# HEBoard_schematic_Ver2.net
KiCad netlist of a schematic drawn in Altium Designer
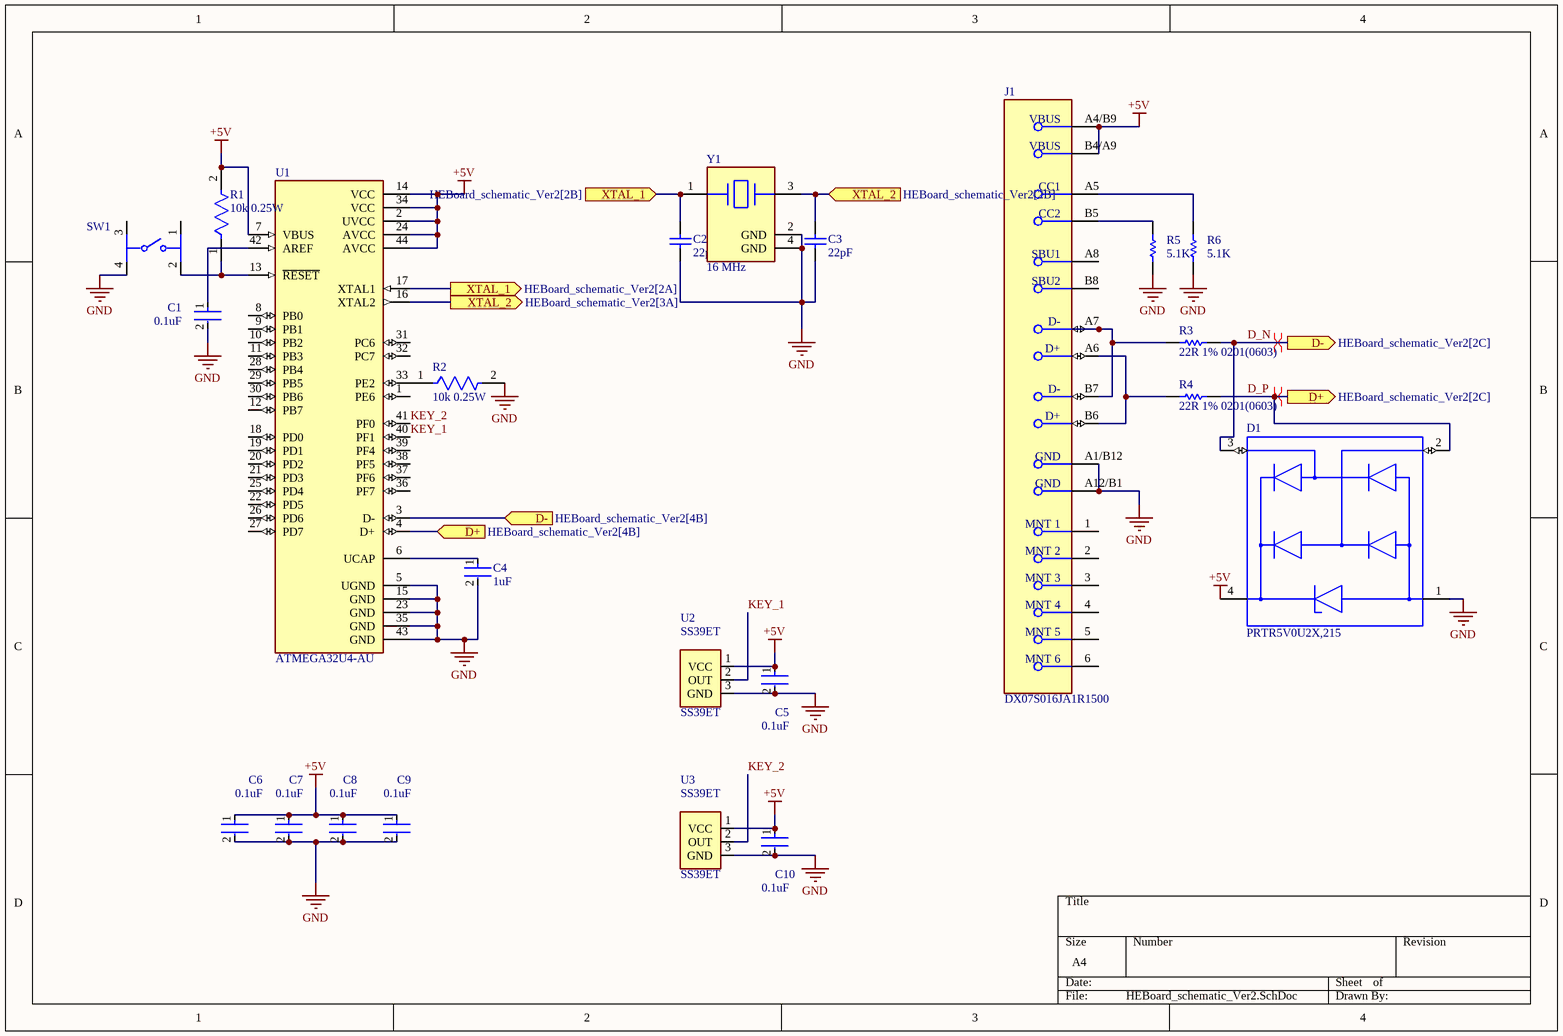
[diagram p0: HEBoard_schematic_Ver2.SchDoc]

(export (version "E")
  (design (tool "Eeschema 10.0.6"))
  (components
    (comp (ref "C1")
      (value "0.1uF")
      (footprint "FP-GRM033-0_03-IPC_C")
      (description "Chip Multilayer Ceramic Capacitors for General Purpose, 0201, 0.10uF, X5R, 15%, 10%, 10V")
      (fields (field (name "TOLERANCE") "10%") (field (name "VOLTAGE") "10V"))
      (libsource (lib "Altium Content Vault") (part "b4654b650e69147ec39a6b967a45e02"))
    )
    (comp (ref "C2")
      (value "22pF")
      (footprint "CAPC1006X50X20ML10T10")
      (fields
        (field (name "PART NUMBER") "0402ZK220GBSTR..")
        (field (name "MANUFACTURER") "AVX Interconnect / Elco")
      )
      (libsource (lib "Altium Content Vault") (part "CAP"))
    )
    (comp (ref "C3")
      (value "22pF")
      (footprint "CAPC1006X50X20ML10T10")
      (fields
        (field (name "PART NUMBER") "0402ZK220GBSTR..")
        (field (name "MANUFACTURER") "AVX Interconnect / Elco")
      )
      (libsource (lib "Altium Content Vault") (part "CAP"))
    )
    (comp (ref "C4")
      (value "1uF")
      (footprint "FP-GRM15-0_1-MFG")
      (description "CAP CER 1UF 10V X5R 0402")
      (fields
        (field (name "OCTOPART") "https://octopart.com/grm155r61a105ke15d-murata-197442")
        (field (name "MANUFACTURER PART NUMBER") "GRM155R61A105KE15D")
      )
      (libsource (lib "Altium Content Vault") (part "02cd4be3c70576c341d710602a673aa"))
    )
    (comp (ref "C5")
      (value "0.1uF")
      (footprint "FP-GRM033-0_03-IPC_C")
      (description "Chip Multilayer Ceramic Capacitors for General Purpose, 0201, 0.10uF, X5R, 15%, 10%, 10V")
      (fields (field (name "TOLERANCE") "10%") (field (name "VOLTAGE") "10V"))
      (libsource (lib "Altium Content Vault") (part "b4654b650e69147ec39a6b967a45e02"))
    )
    (comp (ref "C6")
      (value "0.1uF")
      (footprint "FP-GRM033-0_03-IPC_C")
      (description "Chip Multilayer Ceramic Capacitors for General Purpose, 0201, 0.10uF, X5R, 15%, 10%, 10V")
      (fields (field (name "TOLERANCE") "10%") (field (name "VOLTAGE") "10V"))
      (libsource (lib "Altium Content Vault") (part "b4654b650e69147ec39a6b967a45e02"))
    )
    (comp (ref "C7")
      (value "0.1uF")
      (footprint "FP-GRM033-0_03-IPC_C")
      (description "Chip Multilayer Ceramic Capacitors for General Purpose, 0201, 0.10uF, X5R, 15%, 10%, 10V")
      (fields (field (name "TOLERANCE") "10%") (field (name "VOLTAGE") "10V"))
      (libsource (lib "Altium Content Vault") (part "b4654b650e69147ec39a6b967a45e02"))
    )
    (comp (ref "C8")
      (value "0.1uF")
      (footprint "FP-GRM033-0_03-IPC_C")
      (description "Chip Multilayer Ceramic Capacitors for General Purpose, 0201, 0.10uF, X5R, 15%, 10%, 10V")
      (fields (field (name "TOLERANCE") "10%") (field (name "VOLTAGE") "10V"))
      (libsource (lib "Altium Content Vault") (part "b4654b650e69147ec39a6b967a45e02"))
    )
    (comp (ref "C9")
      (value "0.1uF")
      (footprint "FP-GRM033-0_03-IPC_C")
      (description "Chip Multilayer Ceramic Capacitors for General Purpose, 0201, 0.10uF, X5R, 15%, 10%, 10V")
      (fields (field (name "TOLERANCE") "10%") (field (name "VOLTAGE") "10V"))
      (libsource (lib "Altium Content Vault") (part "b4654b650e69147ec39a6b967a45e02"))
    )
    (comp (ref "C10")
      (value "0.1uF")
      (footprint "FP-GRM033-0_03-IPC_C")
      (description "Chip Multilayer Ceramic Capacitors for General Purpose, 0201, 0.10uF, X5R, 15%, 10%, 10V")
      (fields (field (name "TOLERANCE") "10%") (field (name "VOLTAGE") "10V"))
      (libsource (lib "Altium Content Vault") (part "b4654b650e69147ec39a6b967a45e02"))
    )
    (comp (ref "D1")
      (value "PRTR5V0U2X,215")
      (footprint "FP-SOT143B-MFG")
      (description "TVS DIODE 5.5V SOT143B")
      (libsource (lib "Altium Content Vault") (part "31e4fa1655694efd507c8a671e666ef"))
    )
    (comp (ref "J1")
      (value "DX07S016JA1R1500")
      (footprint "FP-DX07S016JA1R1500-MFG")
      (description "CONN RCP USB2.0 TYP C 24P SMD RA")
      (libsource (lib "Altium Content Vault") (part "7f3e9989102a0f22bff9cb010881d34"))
    )
    (comp (ref "R1")
      (value "10k 0.25W")
      (footprint "FP-RNCP0805-IPC_C")
      (description "10kΩ ±1% 0.25W 0805 High Power Anti-Sulfur Thin Film Chip Resistor")
      (fields (field (name "TOLERANCE") "1%"))
      (libsource (lib "Altium Content Vault") (part "1029c3af85768c4190bb7ad29bc67b5"))
    )
    (comp (ref "R2")
      (value "10k 0.25W")
      (footprint "FP-RNCP0805-IPC_C")
      (description "10kΩ ±1% 0.25W 0805 High Power Anti-Sulfur Thin Film Chip Resistor")
      (fields (field (name "TOLERANCE") "1%"))
      (libsource (lib "Altium Content Vault") (part "1029c3af85768c4190bb7ad29bc67b5"))
    )
    (comp (ref "R3")
      (value "22R 1% 0201(0603)")
      (footprint "RESC0201(0603)_M")
      (description "22R 0.05W 1% 0201 (0603 Metric)  SMD")
      (fields (field (name "POWER") "0.05 W") (field (name "TOLERANCE") "1 %"))
      (libsource (lib "Altium Content Vault") (part "RES"))
    )
    (comp (ref "R4")
      (value "22R 1% 0201(0603)")
      (footprint "RESC0201(0603)_M")
      (description "22R 0.05W 1% 0201 (0603 Metric)  SMD")
      (fields (field (name "POWER") "0.05 W") (field (name "TOLERANCE") "1 %"))
      (libsource (lib "Altium Content Vault") (part "RES"))
    )
    (comp (ref "R5")
      (value "5.1K")
      (footprint "RESC2013X60X30NL20T20")
      (fields (field (name "MANUFACTURER") "KOA Speer") (field (name "PART NUMBER") "RK73H2ATTD5101F"))
      (libsource (lib "Altium Content Vault") (part "RES"))
    )
    (comp (ref "R6")
      (value "5.1K")
      (footprint "RESC2013X60X30NL20T20")
      (fields (field (name "MANUFACTURER") "KOA Speer") (field (name "PART NUMBER") "RK73H2ATTD5101F"))
      (libsource (lib "Altium Content Vault") (part "RES"))
    )
    (comp (ref "SW1")
      (value "~")
      (footprint "FP-PTS645SM43SMTR92LFS-MFG")
      (description "SWITCH TACTILE SPST-NO 0.05A 12V")
      (libsource (lib "Altium Content Vault") (part "1adf0dd01260c80cf25a44bfd6b99ba"))
    )
    (comp (ref "U1")
      (value "ATMEGA32U4-AU")
      (footprint "QFP80P1200X1200X120-44N")
      (description "AVR AVRÂ® ATmega Microcontroller IC 8-Bit 16MHz 32KB (16K x 16) FLASH 44-TQFP (10x10)")
      (fields (field (name "MF") "Microchip Technology"))
      (libsource (lib "Schlib1") (part "ATMEGA32U4-AU"))
    )
    (comp (ref "U2")
      (value "SS39ET")
      (footprint "CHRY-MX1A-11NW_V")
      (description "analog Hall Effect Sensor 1.5 mA 2.7 - 6.5 V dc ¦ Honeywell SS39ET")
      (fields (field (name "MF") "Honeywell Sensing and Productivity Solutions"))
      (libsource (lib "Schlib1") (part "SS39ET"))
    )
    (comp (ref "U3")
      (value "SS39ET")
      (footprint "CHRY-MX1A-11NW_V")
      (description "analog Hall Effect Sensor 1.5 mA 2.7 - 6.5 V dc ¦ Honeywell SS39ET")
      (fields (field (name "MF") "Honeywell Sensing and Productivity Solutions"))
      (libsource (lib "Schlib1") (part "SS39ET"))
    )
    (comp (ref "Y1")
      (value "16 MHz")
      (footprint "FP-ABM8G-MFG")
      (description "Crystal 16MHz ±30ppm (Tol) ±30ppm (Stability) 10pF FUND 80Ω 4-Pin SMD T/R")
      (libsource (lib "Altium Content Vault") (part "48e526d86b7f2615d98721063c72f49"))
    )
  )
  (nets
    (net (code "1") (name "+5V") (class "Default")
      (node (ref "C10") (pin "1") (pinfunction "1_1") (pintype "passive"))
      (node (ref "C5") (pin "1") (pinfunction "1_1") (pintype "passive"))
      (node (ref "C6") (pin "1") (pinfunction "1_1") (pintype "passive"))
      (node (ref "C7") (pin "1") (pinfunction "1_1") (pintype "passive"))
      (node (ref "C8") (pin "1") (pinfunction "1_1") (pintype "passive"))
      (node (ref "C9") (pin "1") (pinfunction "1_1") (pintype "passive"))
      (node (ref "D1") (pin "4") (pinfunction "VCC_4") (pintype "power_in"))
      (node (ref "J1") (pin "A4/B9") (pinfunction "VBUS_A4/B9") (pintype "power_in"))
      (node (ref "J1") (pin "B4/A9") (pinfunction "VBUS_B4/A9") (pintype "power_in"))
      (node (ref "R1") (pin "2") (pinfunction "2_2") (pintype "passive"))
      (node (ref "U1") (pin "14") (pinfunction "VCC_14") (pintype "power_in"))
      (node (ref "U1") (pin "2") (pinfunction "UVCC_2") (pintype "power_in"))
      (node (ref "U1") (pin "24") (pinfunction "AVCC_24") (pintype "power_in"))
      (node (ref "U1") (pin "34") (pinfunction "VCC_34") (pintype "power_in"))
      (node (ref "U1") (pin "44") (pinfunction "AVCC_44") (pintype "power_in"))
      (node (ref "U1") (pin "7") (pinfunction "VBUS_7") (pintype "input"))
      (node (ref "U2") (pin "1") (pinfunction "VCC_1") (pintype "passive"))
      (node (ref "U3") (pin "1") (pinfunction "VCC_1") (pintype "passive"))
    )
    (net (code "2") (name "/D_N") (class "Default")
      (node (ref "D1") (pin "3") (pinfunction "I/O_2_3") (pintype "bidirectional"))
      (node (ref "R3") (pin "2") (pinfunction "2_2") (pintype "passive"))
      (node (ref "U1") (pin "3") (pinfunction "D-_3") (pintype "bidirectional"))
    )
    (net (code "3") (name "/D_P") (class "Default")
      (node (ref "D1") (pin "2") (pinfunction "I/O_1_2") (pintype "bidirectional"))
      (node (ref "R4") (pin "2") (pinfunction "2_2") (pintype "passive"))
      (node (ref "U1") (pin "4") (pinfunction "D+_4") (pintype "bidirectional"))
    )
    (net (code "4") (name "/KEY_1") (class "Default")
      (node (ref "U1") (pin "40") (pinfunction "PF1_40") (pintype "bidirectional"))
      (node (ref "U2") (pin "2") (pinfunction "OUT_2") (pintype "passive"))
    )
    (net (code "5") (name "/KEY_2") (class "Default")
      (node (ref "U1") (pin "41") (pinfunction "PF0_41") (pintype "bidirectional"))
      (node (ref "U3") (pin "2") (pinfunction "OUT_2") (pintype "passive"))
    )
    (net (code "6") (name "/XTAL_1") (class "Default")
      (node (ref "C2") (pin "2") (pinfunction "2_2") (pintype "passive"))
      (node (ref "U1") (pin "17") (pinfunction "XTAL1_17") (pintype "input"))
      (node (ref "Y1") (pin "1") (pinfunction "1_1") (pintype "passive"))
    )
    (net (code "7") (name "/XTAL_2") (class "Default")
      (node (ref "C3") (pin "2") (pinfunction "2_2") (pintype "passive"))
      (node (ref "U1") (pin "16") (pinfunction "XTAL2_16") (pintype "output"))
      (node (ref "Y1") (pin "3") (pinfunction "3_3") (pintype "passive"))
    )
    (net (code "8") (name "GND") (class "Default")
      (node (ref "C1") (pin "2") (pinfunction "2_2") (pintype "passive"))
      (node (ref "C10") (pin "2") (pinfunction "2_2") (pintype "passive"))
      (node (ref "C2") (pin "1") (pinfunction "1_1") (pintype "passive"))
      (node (ref "C3") (pin "1") (pinfunction "1_1") (pintype "passive"))
      (node (ref "C4") (pin "2") (pinfunction "2_2") (pintype "passive"))
      (node (ref "C5") (pin "2") (pinfunction "2_2") (pintype "passive"))
      (node (ref "C6") (pin "2") (pinfunction "2_2") (pintype "passive"))
      (node (ref "C7") (pin "2") (pinfunction "2_2") (pintype "passive"))
      (node (ref "C8") (pin "2") (pinfunction "2_2") (pintype "passive"))
      (node (ref "C9") (pin "2") (pinfunction "2_2") (pintype "passive"))
      (node (ref "D1") (pin "1") (pinfunction "GND_1") (pintype "power_in"))
      (node (ref "J1") (pin "A1/B12") (pinfunction "GND_A1/B12") (pintype "power_in"))
      (node (ref "J1") (pin "A12/B1") (pinfunction "GND_A12/B1") (pintype "power_in"))
      (node (ref "R2") (pin "2") (pinfunction "2_2") (pintype "passive"))
      (node (ref "R5") (pin "1") (pinfunction "1_1") (pintype "passive"))
      (node (ref "R6") (pin "1") (pinfunction "1_1") (pintype "passive"))
      (node (ref "SW1") (pin "4") (pinfunction "4_4") (pintype "passive"))
      (node (ref "U1") (pin "15") (pinfunction "GND_15") (pintype "power_in"))
      (node (ref "U1") (pin "23") (pinfunction "GND_23") (pintype "power_in"))
      (node (ref "U1") (pin "35") (pinfunction "GND_35") (pintype "power_in"))
      (node (ref "U1") (pin "43") (pinfunction "GND_43") (pintype "power_in"))
      (node (ref "U1") (pin "5") (pinfunction "UGND_5") (pintype "power_in"))
      (node (ref "U2") (pin "3") (pinfunction "GND_3") (pintype "passive"))
      (node (ref "U3") (pin "3") (pinfunction "GND_3") (pintype "passive"))
      (node (ref "Y1") (pin "2") (pinfunction "GND_2") (pintype "power_in"))
      (node (ref "Y1") (pin "4") (pinfunction "GND_4") (pintype "power_in"))
    )
    (net (code "9") (name "Net-(J1-CC1)") (class "Default")
      (node (ref "J1") (pin "A5") (pinfunction "CC1_A5") (pintype "passive"))
      (node (ref "R6") (pin "2") (pinfunction "2_2") (pintype "passive"))
    )
    (net (code "10") (name "Net-(J1-CC2)") (class "Default")
      (node (ref "J1") (pin "B5") (pinfunction "CC2_B5") (pintype "passive"))
      (node (ref "R5") (pin "2") (pinfunction "2_2") (pintype "passive"))
    )
    (net (code "11") (name "Net-(J1-D+-PadA6)") (class "Default")
      (node (ref "J1") (pin "A6") (pinfunction "D+_A6") (pintype "bidirectional"))
      (node (ref "J1") (pin "B6") (pinfunction "D+_B6") (pintype "bidirectional"))
      (node (ref "R4") (pin "1") (pinfunction "1_1") (pintype "passive"))
    )
    (net (code "12") (name "Net-(J1-D--PadA7)") (class "Default")
      (node (ref "J1") (pin "A7") (pinfunction "D-_A7") (pintype "bidirectional"))
      (node (ref "J1") (pin "B7") (pinfunction "D-_B7") (pintype "bidirectional"))
      (node (ref "R3") (pin "1") (pinfunction "1_1") (pintype "passive"))
    )
    (net (code "13") (name "Net-(U1-AREF)") (class "Default")
      (node (ref "C1") (pin "1") (pinfunction "1_1") (pintype "passive"))
      (node (ref "U1") (pin "42") (pinfunction "AREF_42") (pintype "input"))
    )
    (net (code "14") (name "Net-(U1-PE2)") (class "Default")
      (node (ref "R2") (pin "1") (pinfunction "1_1") (pintype "passive"))
      (node (ref "U1") (pin "33") (pinfunction "PE2_33") (pintype "bidirectional"))
    )
    (net (code "15") (name "Net-(U1-UCAP)") (class "Default")
      (node (ref "C4") (pin "1") (pinfunction "1_1") (pintype "passive"))
      (node (ref "U1") (pin "6") (pinfunction "UCAP_6") (pintype "passive"))
    )
    (net (code "16") (name "Net-(U1-~{RESET})") (class "Default")
      (node (ref "R1") (pin "1") (pinfunction "1_1") (pintype "passive"))
      (node (ref "SW1") (pin "2") (pinfunction "2_2") (pintype "passive"))
      (node (ref "U1") (pin "13") (pinfunction "~{RESET}_13") (pintype "input"))
    )
    (net (code "17") (name "unconnected-(J1-MNT_1-Pad1)") (class "Default")
      (node (ref "J1") (pin "1") (pinfunction "MNT_1_1") (pintype "passive"))
    )
    (net (code "18") (name "unconnected-(J1-MNT_2-Pad2)") (class "Default")
      (node (ref "J1") (pin "2") (pinfunction "MNT_2_2") (pintype "passive"))
    )
    (net (code "19") (name "unconnected-(J1-MNT_3-Pad3)") (class "Default")
      (node (ref "J1") (pin "3") (pinfunction "MNT_3_3") (pintype "passive"))
    )
    (net (code "20") (name "unconnected-(J1-MNT_4-Pad4)") (class "Default")
      (node (ref "J1") (pin "4") (pinfunction "MNT_4_4") (pintype "passive"))
    )
    (net (code "21") (name "unconnected-(J1-MNT_5-Pad5)") (class "Default")
      (node (ref "J1") (pin "5") (pinfunction "MNT_5_5") (pintype "passive"))
    )
    (net (code "22") (name "unconnected-(J1-MNT_6-Pad6)") (class "Default")
      (node (ref "J1") (pin "6") (pinfunction "MNT_6_6") (pintype "passive"))
    )
    (net (code "23") (name "unconnected-(J1-SBU1-PadA8)") (class "Default")
      (node (ref "J1") (pin "A8") (pinfunction "SBU1_A8") (pintype "passive"))
    )
    (net (code "24") (name "unconnected-(J1-SBU2-PadB8)") (class "Default")
      (node (ref "J1") (pin "B8") (pinfunction "SBU2_B8") (pintype "passive"))
    )
    (net (code "25") (name "unconnected-(SW1-Pad1)") (class "Default")
      (node (ref "SW1") (pin "1") (pinfunction "1_1") (pintype "passive"))
    )
    (net (code "26") (name "unconnected-(SW1-Pad3)") (class "Default")
      (node (ref "SW1") (pin "3") (pinfunction "3_3") (pintype "passive"))
    )
    (net (code "27") (name "unconnected-(U1-PB0-Pad8)") (class "Default")
      (node (ref "U1") (pin "8") (pinfunction "PB0_8") (pintype "bidirectional"))
    )
    (net (code "28") (name "unconnected-(U1-PB1-Pad9)") (class "Default")
      (node (ref "U1") (pin "9") (pinfunction "PB1_9") (pintype "bidirectional"))
    )
    (net (code "29") (name "unconnected-(U1-PB2-Pad10)") (class "Default")
      (node (ref "U1") (pin "10") (pinfunction "PB2_10") (pintype "bidirectional"))
    )
    (net (code "30") (name "unconnected-(U1-PB3-Pad11)") (class "Default")
      (node (ref "U1") (pin "11") (pinfunction "PB3_11") (pintype "bidirectional"))
    )
    (net (code "31") (name "unconnected-(U1-PB4-Pad28)") (class "Default")
      (node (ref "U1") (pin "28") (pinfunction "PB4_28") (pintype "bidirectional"))
    )
    (net (code "32") (name "unconnected-(U1-PB5-Pad29)") (class "Default")
      (node (ref "U1") (pin "29") (pinfunction "PB5_29") (pintype "bidirectional"))
    )
    (net (code "33") (name "unconnected-(U1-PB6-Pad30)") (class "Default")
      (node (ref "U1") (pin "30") (pinfunction "PB6_30") (pintype "bidirectional"))
    )
    (net (code "34") (name "unconnected-(U1-PB7-Pad12)") (class "Default")
      (node (ref "U1") (pin "12") (pinfunction "PB7_12") (pintype "bidirectional"))
    )
    (net (code "35") (name "unconnected-(U1-PC6-Pad31)") (class "Default")
      (node (ref "U1") (pin "31") (pinfunction "PC6_31") (pintype "bidirectional"))
    )
    (net (code "36") (name "unconnected-(U1-PC7-Pad32)") (class "Default")
      (node (ref "U1") (pin "32") (pinfunction "PC7_32") (pintype "bidirectional"))
    )
    (net (code "37") (name "unconnected-(U1-PD0-Pad18)") (class "Default")
      (node (ref "U1") (pin "18") (pinfunction "PD0_18") (pintype "bidirectional"))
    )
    (net (code "38") (name "unconnected-(U1-PD1-Pad19)") (class "Default")
      (node (ref "U1") (pin "19") (pinfunction "PD1_19") (pintype "bidirectional"))
    )
    (net (code "39") (name "unconnected-(U1-PD2-Pad20)") (class "Default")
      (node (ref "U1") (pin "20") (pinfunction "PD2_20") (pintype "bidirectional"))
    )
    (net (code "40") (name "unconnected-(U1-PD3-Pad21)") (class "Default")
      (node (ref "U1") (pin "21") (pinfunction "PD3_21") (pintype "bidirectional"))
    )
    (net (code "41") (name "unconnected-(U1-PD4-Pad25)") (class "Default")
      (node (ref "U1") (pin "25") (pinfunction "PD4_25") (pintype "bidirectional"))
    )
    (net (code "42") (name "unconnected-(U1-PD5-Pad22)") (class "Default")
      (node (ref "U1") (pin "22") (pinfunction "PD5_22") (pintype "bidirectional"))
    )
    (net (code "43") (name "unconnected-(U1-PD6-Pad26)") (class "Default")
      (node (ref "U1") (pin "26") (pinfunction "PD6_26") (pintype "bidirectional"))
    )
    (net (code "44") (name "unconnected-(U1-PD7-Pad27)") (class "Default")
      (node (ref "U1") (pin "27") (pinfunction "PD7_27") (pintype "bidirectional"))
    )
    (net (code "45") (name "unconnected-(U1-PE6-Pad1)") (class "Default")
      (node (ref "U1") (pin "1") (pinfunction "PE6_1") (pintype "bidirectional"))
    )
    (net (code "46") (name "unconnected-(U1-PF4-Pad39)") (class "Default")
      (node (ref "U1") (pin "39") (pinfunction "PF4_39") (pintype "bidirectional"))
    )
    (net (code "47") (name "unconnected-(U1-PF5-Pad38)") (class "Default")
      (node (ref "U1") (pin "38") (pinfunction "PF5_38") (pintype "bidirectional"))
    )
    (net (code "48") (name "unconnected-(U1-PF6-Pad37)") (class "Default")
      (node (ref "U1") (pin "37") (pinfunction "PF6_37") (pintype "bidirectional"))
    )
    (net (code "49") (name "unconnected-(U1-PF7-Pad36)") (class "Default")
      (node (ref "U1") (pin "36") (pinfunction "PF7_36") (pintype "bidirectional"))
    )
  )
)
